# Keypad.net
KiCad netlist of a schematic drawn in Altium Designer
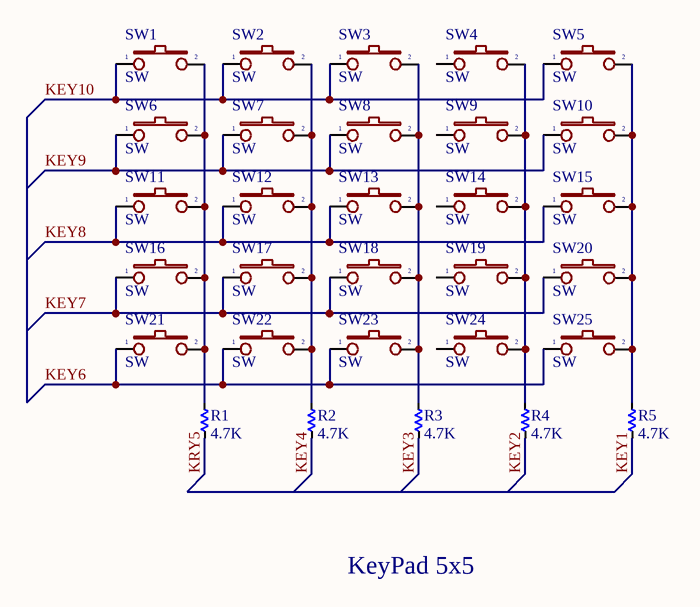
[diagram p0: Keypad.SchDoc]

(export (version "E")
  (design (tool "Eeschema 10.0.6"))
  (components
    (comp (ref "R1")
      (value "4.7K")
      (footprint "RES-1/2W")
      (description "Res")
      (fields
        (field (name "MANUFACTURER") "Generic Components")
        (field (name "PUBLISHER") "Altium Hobart Technology Centre")
      )
      (libsource (lib "LIBRARY") (part "Res"))
    )
    (comp (ref "R2")
      (value "4.7K")
      (footprint "RES-1/2W")
      (description "Res")
      (fields
        (field (name "MANUFACTURER") "Generic Components")
        (field (name "PUBLISHER") "Altium Hobart Technology Centre")
      )
      (libsource (lib "LIBRARY") (part "Res"))
    )
    (comp (ref "R3")
      (value "4.7K")
      (footprint "RES-1/2W")
      (description "Res")
      (fields
        (field (name "MANUFACTURER") "Generic Components")
        (field (name "PUBLISHER") "Altium Hobart Technology Centre")
      )
      (libsource (lib "LIBRARY") (part "Res"))
    )
    (comp (ref "R4")
      (value "4.7K")
      (footprint "RES-1/2W")
      (description "Res")
      (fields
        (field (name "MANUFACTURER") "Generic Components")
        (field (name "PUBLISHER") "Altium Hobart Technology Centre")
      )
      (libsource (lib "LIBRARY") (part "Res"))
    )
    (comp (ref "R5")
      (value "4.7K")
      (footprint "RES-1/2W")
      (description "Res")
      (fields
        (field (name "MANUFACTURER") "Generic Components")
        (field (name "PUBLISHER") "Altium Hobart Technology Centre")
      )
      (libsource (lib "LIBRARY") (part "Res"))
    )
    (comp (ref "SW1")
      (value "SW")
      (footprint "SW-DIP1-1")
      (description "Switch button 2 pin")
      (libsource (lib "LIBRARY") (part "SW2"))
    )
    (comp (ref "SW2")
      (value "SW")
      (footprint "SW-DIP1-1")
      (description "Switch button 2 pin")
      (libsource (lib "LIBRARY") (part "SW2"))
    )
    (comp (ref "SW3")
      (value "SW")
      (footprint "SW-DIP1-1")
      (description "Switch button 2 pin")
      (libsource (lib "LIBRARY") (part "SW2"))
    )
    (comp (ref "SW4")
      (value "SW")
      (footprint "SW-DIP1-1")
      (description "Switch button 2 pin")
      (libsource (lib "LIBRARY") (part "SW2"))
    )
    (comp (ref "SW5")
      (value "SW")
      (footprint "SW-DIP1-1")
      (description "Switch button 2 pin")
      (libsource (lib "LIBRARY") (part "SW2"))
    )
    (comp (ref "SW6")
      (value "SW")
      (footprint "SW-DIP1-1")
      (description "Switch button 2 pin")
      (libsource (lib "LIBRARY") (part "SW2"))
    )
    (comp (ref "SW7")
      (value "SW")
      (footprint "SW-DIP1-1")
      (description "Switch button 2 pin")
      (libsource (lib "LIBRARY") (part "SW2"))
    )
    (comp (ref "SW8")
      (value "SW")
      (footprint "SW-DIP1-1")
      (description "Switch button 2 pin")
      (libsource (lib "LIBRARY") (part "SW2"))
    )
    (comp (ref "SW9")
      (value "SW")
      (footprint "SW-DIP1-1")
      (description "Switch button 2 pin")
      (libsource (lib "LIBRARY") (part "SW2"))
    )
    (comp (ref "SW10")
      (value "SW")
      (footprint "SW-DIP1-1")
      (description "Switch button 2 pin")
      (libsource (lib "LIBRARY") (part "SW2"))
    )
    (comp (ref "SW11")
      (value "SW")
      (footprint "SW-DIP1-1")
      (description "Switch button 2 pin")
      (libsource (lib "LIBRARY") (part "SW2"))
    )
    (comp (ref "SW12")
      (value "SW")
      (footprint "SW-DIP1-1")
      (description "Switch button 2 pin")
      (libsource (lib "LIBRARY") (part "SW2"))
    )
    (comp (ref "SW13")
      (value "SW")
      (footprint "SW-DIP1-1")
      (description "Switch button 2 pin")
      (libsource (lib "LIBRARY") (part "SW2"))
    )
    (comp (ref "SW14")
      (value "SW")
      (footprint "SW-DIP1-1")
      (description "Switch button 2 pin")
      (libsource (lib "LIBRARY") (part "SW2"))
    )
    (comp (ref "SW15")
      (value "SW")
      (footprint "SW-DIP1-1")
      (description "Switch button 2 pin")
      (libsource (lib "LIBRARY") (part "SW2"))
    )
    (comp (ref "SW16")
      (value "SW")
      (footprint "SW-DIP1-1")
      (description "Switch button 2 pin")
      (libsource (lib "LIBRARY") (part "SW2"))
    )
    (comp (ref "SW17")
      (value "SW")
      (footprint "SW-DIP1-1")
      (description "Switch button 2 pin")
      (libsource (lib "LIBRARY") (part "SW2"))
    )
    (comp (ref "SW18")
      (value "SW")
      (footprint "SW-DIP1-1")
      (description "Switch button 2 pin")
      (libsource (lib "LIBRARY") (part "SW2"))
    )
    (comp (ref "SW19")
      (value "SW")
      (footprint "SW-DIP1-1")
      (description "Switch button 2 pin")
      (libsource (lib "LIBRARY") (part "SW2"))
    )
    (comp (ref "SW20")
      (value "SW")
      (footprint "SW-DIP1-1")
      (description "Switch button 2 pin")
      (libsource (lib "LIBRARY") (part "SW2"))
    )
    (comp (ref "SW21")
      (value "SW")
      (footprint "SW-DIP1-1")
      (description "Switch button 2 pin")
      (libsource (lib "LIBRARY") (part "SW2"))
    )
    (comp (ref "SW22")
      (value "SW")
      (footprint "SW-DIP1-1")
      (description "Switch button 2 pin")
      (libsource (lib "LIBRARY") (part "SW2"))
    )
    (comp (ref "SW23")
      (value "SW")
      (footprint "SW-DIP1-1")
      (description "Switch button 2 pin")
      (libsource (lib "LIBRARY") (part "SW2"))
    )
    (comp (ref "SW24")
      (value "SW")
      (footprint "SW-DIP1-1")
      (description "Switch button 2 pin")
      (libsource (lib "LIBRARY") (part "SW2"))
    )
    (comp (ref "SW25")
      (value "SW")
      (footprint "SW-DIP1-1")
      (description "Switch button 2 pin")
      (libsource (lib "LIBRARY") (part "SW2"))
    )
  )
  (nets
    (net (code "1") (name "/KEY1") (class "Default")
      (node (ref "R5") (pin "2") (pinfunction "2_2") (pintype "passive"))
    )
    (net (code "2") (name "/KEY2") (class "Default")
      (node (ref "R4") (pin "2") (pinfunction "2_2") (pintype "passive"))
    )
    (net (code "3") (name "/KEY3") (class "Default")
      (node (ref "R3") (pin "2") (pinfunction "2_2") (pintype "passive"))
    )
    (net (code "4") (name "/KEY4") (class "Default")
      (node (ref "R2") (pin "2") (pinfunction "2_2") (pintype "passive"))
    )
    (net (code "5") (name "/KEY6") (class "Default")
      (node (ref "SW21") (pin "1") (pinfunction "1_1") (pintype "passive"))
      (node (ref "SW22") (pin "1") (pinfunction "1_1") (pintype "passive"))
      (node (ref "SW23") (pin "1") (pinfunction "1_1") (pintype "passive"))
      (node (ref "SW25") (pin "1") (pinfunction "1_1") (pintype "passive"))
    )
    (net (code "6") (name "/KEY7") (class "Default")
      (node (ref "SW16") (pin "1") (pinfunction "1_1") (pintype "passive"))
      (node (ref "SW17") (pin "1") (pinfunction "1_1") (pintype "passive"))
      (node (ref "SW18") (pin "1") (pinfunction "1_1") (pintype "passive"))
      (node (ref "SW20") (pin "1") (pinfunction "1_1") (pintype "passive"))
    )
    (net (code "7") (name "/KEY8") (class "Default")
      (node (ref "SW11") (pin "1") (pinfunction "1_1") (pintype "passive"))
      (node (ref "SW12") (pin "1") (pinfunction "1_1") (pintype "passive"))
      (node (ref "SW13") (pin "1") (pinfunction "1_1") (pintype "passive"))
      (node (ref "SW15") (pin "1") (pinfunction "1_1") (pintype "passive"))
    )
    (net (code "8") (name "/KEY9") (class "Default")
      (node (ref "SW10") (pin "1") (pinfunction "1_1") (pintype "passive"))
      (node (ref "SW6") (pin "1") (pinfunction "1_1") (pintype "passive"))
      (node (ref "SW7") (pin "1") (pinfunction "1_1") (pintype "passive"))
      (node (ref "SW8") (pin "1") (pinfunction "1_1") (pintype "passive"))
    )
    (net (code "9") (name "/KEY10") (class "Default")
      (node (ref "SW1") (pin "1") (pinfunction "1_1") (pintype "passive"))
      (node (ref "SW2") (pin "1") (pinfunction "1_1") (pintype "passive"))
      (node (ref "SW3") (pin "1") (pinfunction "1_1") (pintype "passive"))
      (node (ref "SW5") (pin "1") (pinfunction "1_1") (pintype "passive"))
    )
    (net (code "10") (name "/KRY5") (class "Default")
      (node (ref "R1") (pin "2") (pinfunction "2_2") (pintype "passive"))
    )
    (net (code "11") (name "Net-(R1-Pad1)") (class "Default")
      (node (ref "R1") (pin "1") (pinfunction "1_1") (pintype "passive"))
      (node (ref "SW1") (pin "2") (pinfunction "2_2") (pintype "passive"))
      (node (ref "SW11") (pin "2") (pinfunction "2_2") (pintype "passive"))
      (node (ref "SW16") (pin "2") (pinfunction "2_2") (pintype "passive"))
      (node (ref "SW21") (pin "2") (pinfunction "2_2") (pintype "passive"))
      (node (ref "SW6") (pin "2") (pinfunction "2_2") (pintype "passive"))
    )
    (net (code "12") (name "Net-(R2-Pad1)") (class "Default")
      (node (ref "R2") (pin "1") (pinfunction "1_1") (pintype "passive"))
      (node (ref "SW12") (pin "2") (pinfunction "2_2") (pintype "passive"))
      (node (ref "SW17") (pin "2") (pinfunction "2_2") (pintype "passive"))
      (node (ref "SW2") (pin "2") (pinfunction "2_2") (pintype "passive"))
      (node (ref "SW22") (pin "2") (pinfunction "2_2") (pintype "passive"))
      (node (ref "SW7") (pin "2") (pinfunction "2_2") (pintype "passive"))
    )
    (net (code "13") (name "Net-(R3-Pad1)") (class "Default")
      (node (ref "R3") (pin "1") (pinfunction "1_1") (pintype "passive"))
      (node (ref "SW13") (pin "2") (pinfunction "2_2") (pintype "passive"))
      (node (ref "SW18") (pin "2") (pinfunction "2_2") (pintype "passive"))
      (node (ref "SW23") (pin "2") (pinfunction "2_2") (pintype "passive"))
      (node (ref "SW3") (pin "2") (pinfunction "2_2") (pintype "passive"))
      (node (ref "SW8") (pin "2") (pinfunction "2_2") (pintype "passive"))
    )
    (net (code "14") (name "Net-(R4-Pad1)") (class "Default")
      (node (ref "R4") (pin "1") (pinfunction "1_1") (pintype "passive"))
      (node (ref "SW14") (pin "2") (pinfunction "2_2") (pintype "passive"))
      (node (ref "SW19") (pin "2") (pinfunction "2_2") (pintype "passive"))
      (node (ref "SW24") (pin "2") (pinfunction "2_2") (pintype "passive"))
      (node (ref "SW4") (pin "2") (pinfunction "2_2") (pintype "passive"))
      (node (ref "SW9") (pin "2") (pinfunction "2_2") (pintype "passive"))
    )
    (net (code "15") (name "Net-(R5-Pad1)") (class "Default")
      (node (ref "R5") (pin "1") (pinfunction "1_1") (pintype "passive"))
      (node (ref "SW10") (pin "2") (pinfunction "2_2") (pintype "passive"))
      (node (ref "SW15") (pin "2") (pinfunction "2_2") (pintype "passive"))
      (node (ref "SW20") (pin "2") (pinfunction "2_2") (pintype "passive"))
      (node (ref "SW25") (pin "2") (pinfunction "2_2") (pintype "passive"))
      (node (ref "SW5") (pin "2") (pinfunction "2_2") (pintype "passive"))
    )
    (net (code "16") (name "unconnected-(SW4-Pad1)") (class "Default")
      (node (ref "SW4") (pin "1") (pinfunction "1_1") (pintype "passive"))
    )
    (net (code "17") (name "unconnected-(SW9-Pad1)") (class "Default")
      (node (ref "SW9") (pin "1") (pinfunction "1_1") (pintype "passive"))
    )
    (net (code "18") (name "unconnected-(SW14-Pad1)") (class "Default")
      (node (ref "SW14") (pin "1") (pinfunction "1_1") (pintype "passive"))
    )
    (net (code "19") (name "unconnected-(SW19-Pad1)") (class "Default")
      (node (ref "SW19") (pin "1") (pinfunction "1_1") (pintype "passive"))
    )
    (net (code "20") (name "unconnected-(SW24-Pad1)") (class "Default")
      (node (ref "SW24") (pin "1") (pinfunction "1_1") (pintype "passive"))
    )
  )
)
